# SpringReverbRev2_combined.net
KiCad netlist of a schematic drawn in EAGLE
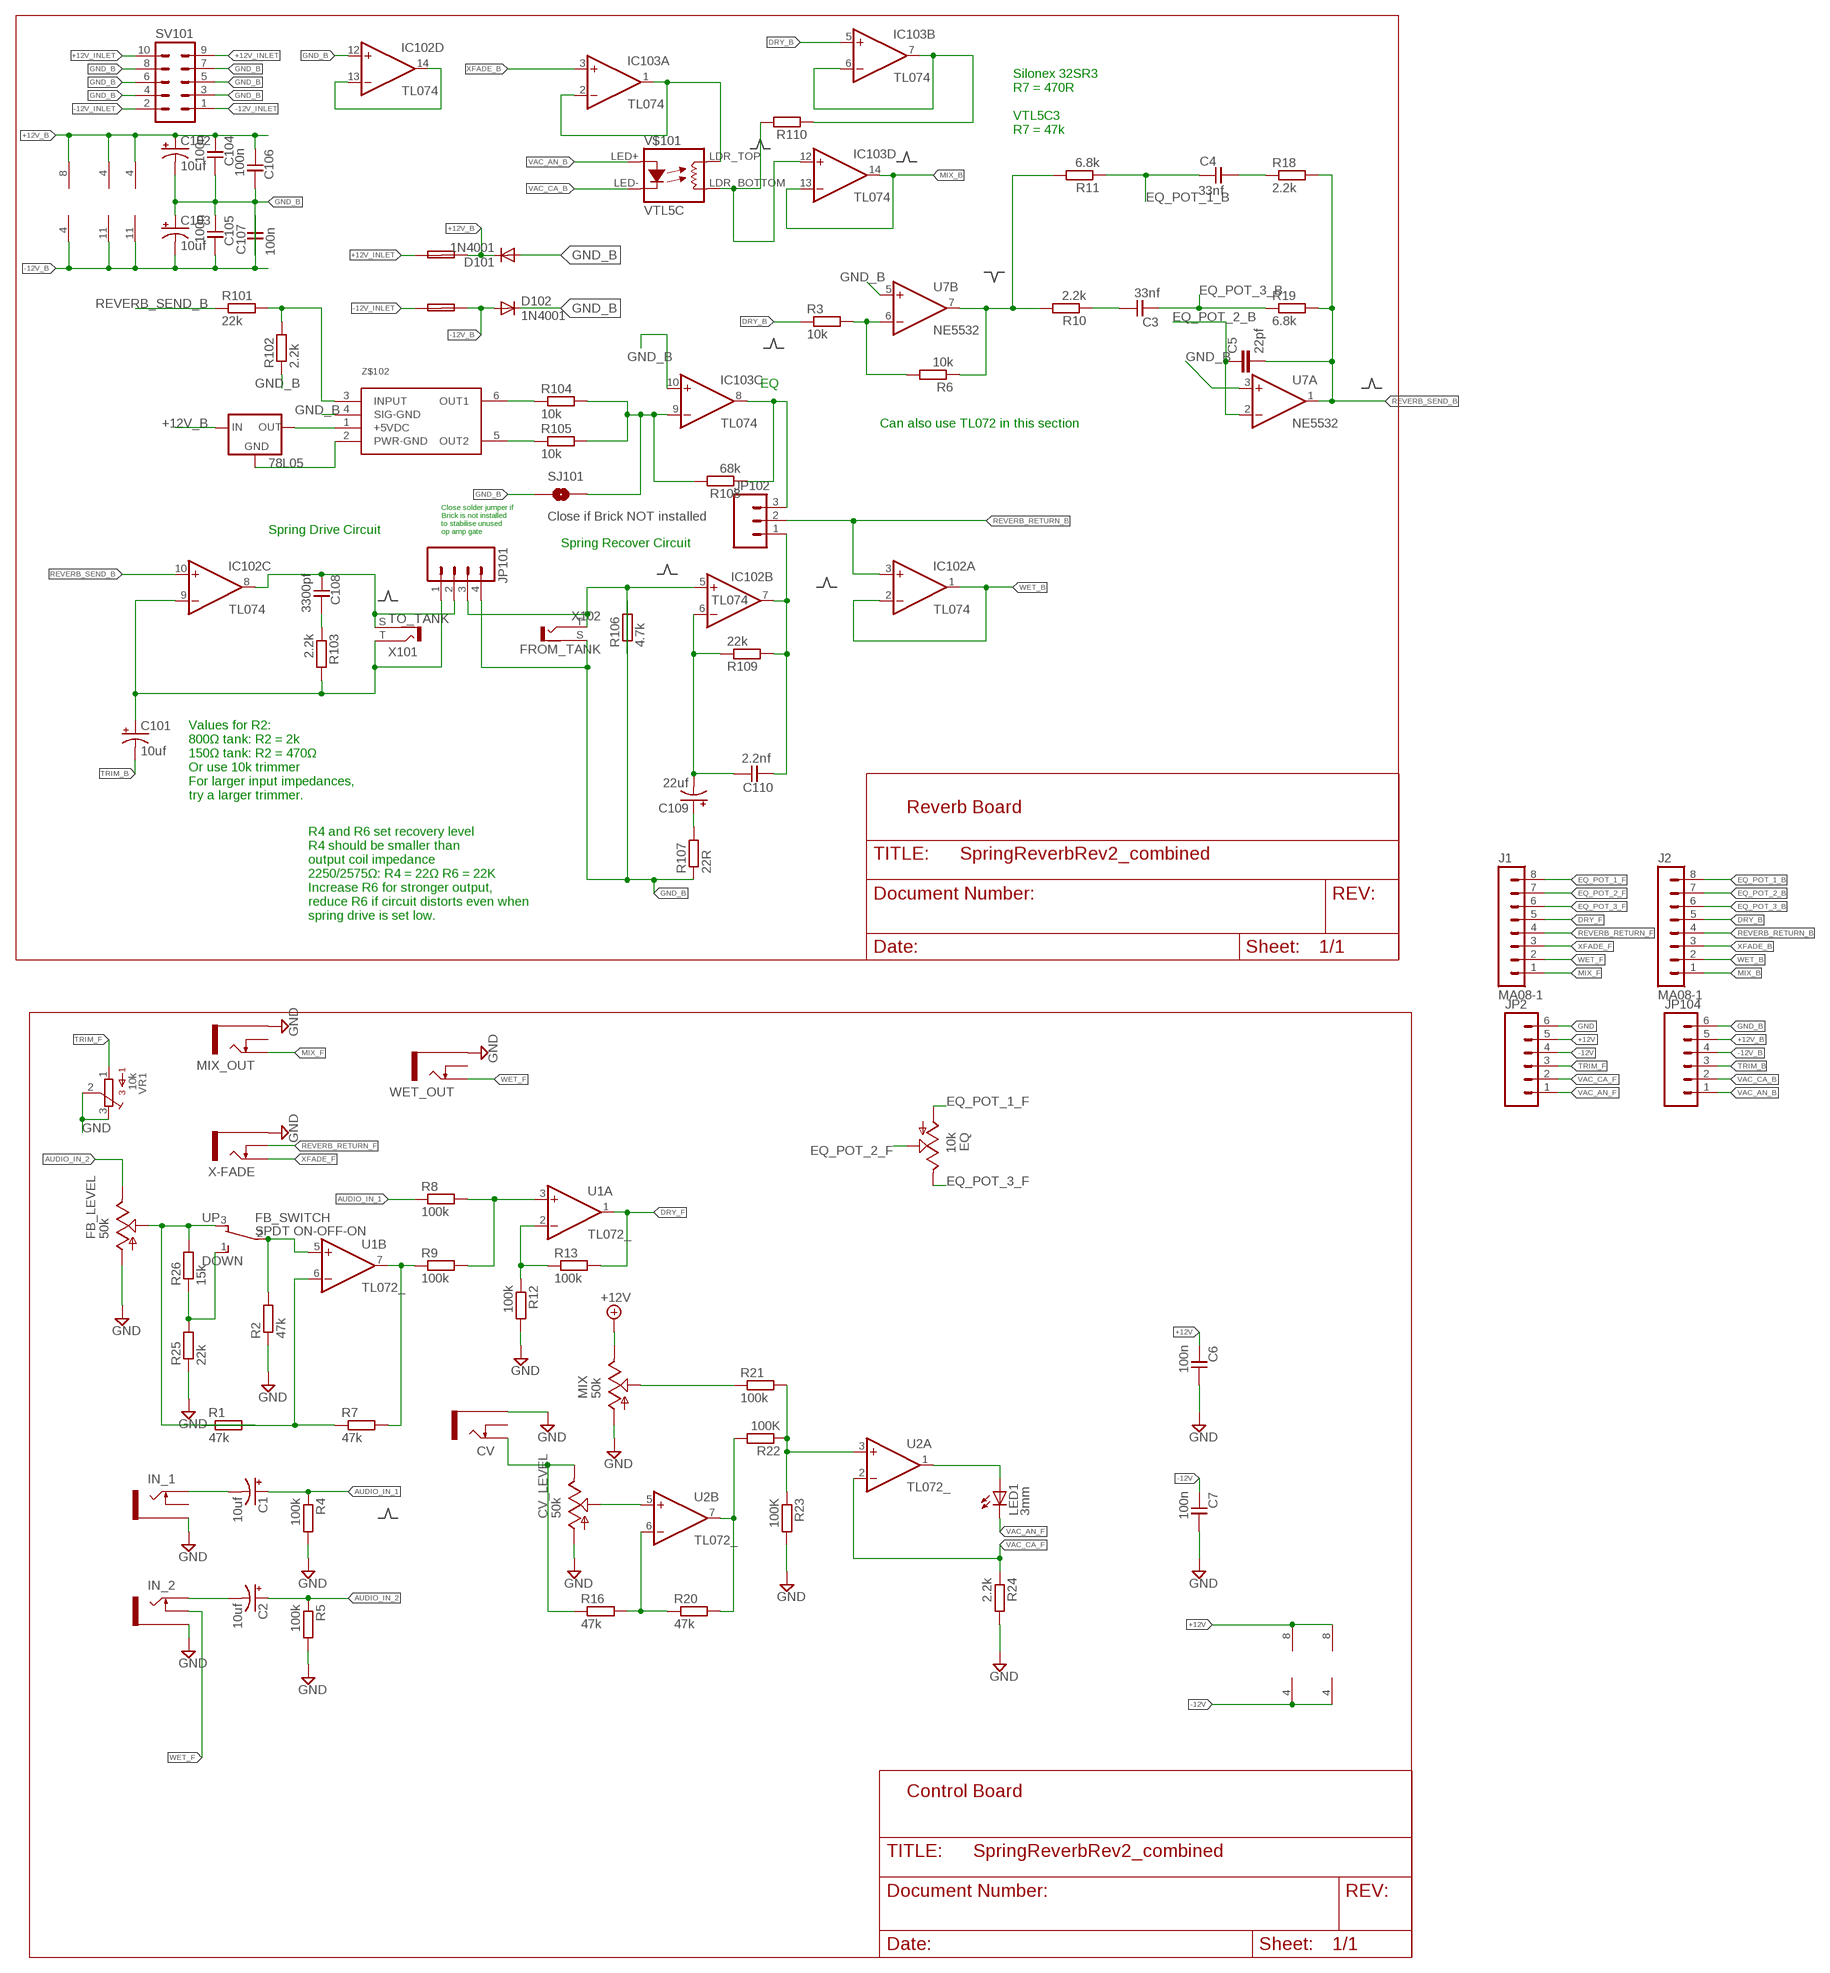
[diagram p0: schematic, sheet 1]

(export (version "E")
  (design (tool "Eeschema 10.0.6"))
  (components
    (comp (ref "78L05")
      (value "78LXX")
      (footprint "eagle-import:78LXX")
      (libsource (lib "eagle-import") (part "78LXX"))
    )
    (comp (ref "C1")
      (value "10uf")
      (footprint "eagle-import:050_020")
      (libsource (lib "eagle-import") (part "050"))
    )
    (comp (ref "C2")
      (value "10uf")
      (footprint "eagle-import:050_020")
      (libsource (lib "eagle-import") (part "050"))
    )
    (comp (ref "C3")
      (value "33nf")
      (footprint "eagle-import:C050-024X044")
      (libsource (lib "eagle-import") (part "C-EU050-024X044"))
    )
    (comp (ref "C4")
      (value "33nf")
      (footprint "eagle-import:C050-024X044")
      (libsource (lib "eagle-import") (part "C-EU050-024X044"))
    )
    (comp (ref "C5")
      (value "22pf")
      (footprint "eagle-import:050X030_025")
      (libsource (lib "eagle-import") (part "050X030_0251"))
    )
    (comp (ref "C6")
      (value "100n")
      (footprint "eagle-import:C050-024X044")
      (libsource (lib "eagle-import") (part "C-EU050-024X044"))
    )
    (comp (ref "C7")
      (value "100n")
      (footprint "eagle-import:C050-024X044")
      (libsource (lib "eagle-import") (part "C-EU050-024X044"))
    )
    (comp (ref "C101")
      (value "10uf")
      (footprint "eagle-import:CPOL-RADIAL-10UF-25V")
      (libsource (lib "eagle-import") (part "CAP_POLPTH2"))
    )
    (comp (ref "C102")
      (value "10uf")
      (footprint "eagle-import:CPOL-RADIAL-10UF-25V")
      (libsource (lib "eagle-import") (part "CAP_POLPTH2"))
    )
    (comp (ref "C103")
      (value "10uf")
      (footprint "eagle-import:CPOL-RADIAL-10UF-25V")
      (libsource (lib "eagle-import") (part "CAP_POLPTH2"))
    )
    (comp (ref "C104")
      (value "100n")
      (footprint "eagle-import:C050-024X044")
      (libsource (lib "eagle-import") (part "C-EU050-024X044"))
    )
    (comp (ref "C105")
      (value "100n")
      (footprint "eagle-import:C050-024X044")
      (libsource (lib "eagle-import") (part "C-EU050-024X044"))
    )
    (comp (ref "C106")
      (value "100n")
      (footprint "eagle-import:C050-024X044")
      (libsource (lib "eagle-import") (part "C-EU050-024X044"))
    )
    (comp (ref "C107")
      (value "100n")
      (footprint "eagle-import:C050-024X044")
      (libsource (lib "eagle-import") (part "C-EU050-024X044"))
    )
    (comp (ref "C108")
      (value "3300pf")
      (footprint "eagle-import:C050-024X044")
      (libsource (lib "eagle-import") (part "C-EU050-024X044"))
    )
    (comp (ref "C109")
      (value "22uf")
      (footprint "eagle-import:CPOL-RADIAL-10UF-25V")
      (libsource (lib "eagle-import") (part "CAP_POLPTH2"))
    )
    (comp (ref "C110")
      (value "2.2nf")
      (footprint "eagle-import:C050-024X044")
      (libsource (lib "eagle-import") (part "C-EU050-024X044"))
    )
    (comp (ref "CV")
      (value "THONKICONNNEW")
      (footprint "eagle-import:WQP-PJ301M-12_JACK")
      (libsource (lib "eagle-import") (part "THONKICONNNEW"))
    )
    (comp (ref "CV_LEVEL")
      (value "50k")
      (footprint "eagle-import:EVUF")
      (libsource (lib "eagle-import") (part "ALPHA-9MMAF2"))
    )
    (comp (ref "D101")
      (value "1N4001")
      (footprint "eagle-import:DO41-10")
      (libsource (lib "eagle-import") (part "1N4004"))
    )
    (comp (ref "D102")
      (value "1N4001")
      (footprint "eagle-import:DO41-10")
      (libsource (lib "eagle-import") (part "1N4004"))
    )
    (comp (ref "EQ")
      (value "10k")
      (footprint "eagle-import:EVUF")
      (libsource (lib "eagle-import") (part "ALPHA-9MMAF2"))
    )
    (comp (ref "F101")
      (value "FUSE")
      (footprint "eagle-import:C050H075X075")
      (libsource (lib "eagle-import") (part "PTC_FUSEPOLY_FUSE"))
    )
    (comp (ref "F102")
      (value "FUSE")
      (footprint "eagle-import:C050H075X075")
      (libsource (lib "eagle-import") (part "PTC_FUSEPOLY_FUSE"))
    )
    (comp (ref "FB_LEVEL")
      (value "50k")
      (footprint "eagle-import:EVUF")
      (libsource (lib "eagle-import") (part "ALPHA-9MMAF2"))
    )
    (comp (ref "FB_SWITCH")
      (value "SPDT ON-OFF-ON")
      (footprint "eagle-import:SPDT-VERTICAL-TOP-SUBMINI-MULTICOMP")
      (libsource (lib "eagle-import") (part "SPDT-VERTICAL-UPTOP-SUBMINI"))
    )
    (comp (ref "IC102")
      (value "TL074")
      (footprint "eagle-import:DIL14")
      (libsource (lib "eagle-import") (part "TL074P"))
    )
    (comp (ref "IC103")
      (value "TL074")
      (footprint "eagle-import:DIL14")
      (libsource (lib "eagle-import") (part "TL074P"))
    )
    (comp (ref "IN_1")
      (value "THONKICONNNEW")
      (footprint "eagle-import:WQP-PJ301M-12_JACK")
      (libsource (lib "eagle-import") (part "THONKICONNNEW"))
    )
    (comp (ref "IN_2")
      (value "THONKICONNNEW")
      (footprint "eagle-import:WQP-PJ301M-12_JACK")
      (libsource (lib "eagle-import") (part "THONKICONNNEW"))
    )
    (comp (ref "J1")
      (value "MA08-1")
      (footprint "eagle-import:MA08-1")
      (libsource (lib "eagle-import") (part "MA08-1"))
    )
    (comp (ref "J2")
      (value "MA08-1")
      (footprint "eagle-import:MA08-1")
      (libsource (lib "eagle-import") (part "MA08-1"))
    )
    (comp (ref "JP2")
      (value "M06SIP")
      (footprint "eagle-import:1X06")
      (libsource (lib "eagle-import") (part "M06SIP"))
    )
    (comp (ref "JP101")
      (value "M04POLAR")
      (footprint "eagle-import:MOLEX-1X4")
      (libsource (lib "eagle-import") (part "M04POLAR"))
    )
    (comp (ref "JP102")
      (value "M03LOCK_NO_SILK")
      (footprint "eagle-import:1X03_LOCK_NO_SILK")
      (libsource (lib "eagle-import") (part "M03LOCK_NO_SILK"))
    )
    (comp (ref "JP104")
      (value "M06SIP")
      (footprint "eagle-import:1X06")
      (libsource (lib "eagle-import") (part "M06SIP"))
    )
    (comp (ref "LED1")
      (value "3mm")
      (footprint "eagle-import:LED3MM")
      (libsource (lib "eagle-import") (part "LED3MM"))
    )
    (comp (ref "MIX")
      (value "50k")
      (footprint "eagle-import:EVUF")
      (libsource (lib "eagle-import") (part "ALPHA-9MMAF2"))
    )
    (comp (ref "MIX_OUT")
      (value "THONKICONNNEW")
      (footprint "eagle-import:WQP-PJ301M-12_JACK")
      (libsource (lib "eagle-import") (part "THONKICONNNEW"))
    )
    (comp (ref "R1")
      (value "47k")
      (footprint "eagle-import:7MM_RESISTOR")
      (libsource (lib "eagle-import") (part "RESISTOR7MM"))
    )
    (comp (ref "R2")
      (value "47k")
      (footprint "eagle-import:7MM_RESISTOR")
      (libsource (lib "eagle-import") (part "RESISTOR7MM"))
    )
    (comp (ref "R3")
      (value "10k")
      (footprint "eagle-import:7MM_RESISTOR")
      (libsource (lib "eagle-import") (part "RESISTOR7MM"))
    )
    (comp (ref "R4")
      (value "100k")
      (footprint "eagle-import:7MM_RESISTOR")
      (libsource (lib "eagle-import") (part "RESISTOR7MM"))
    )
    (comp (ref "R5")
      (value "100k")
      (footprint "eagle-import:7MM_RESISTOR")
      (libsource (lib "eagle-import") (part "RESISTOR7MM"))
    )
    (comp (ref "R6")
      (value "10k")
      (footprint "eagle-import:7MM_RESISTOR")
      (libsource (lib "eagle-import") (part "RESISTOR7MM"))
    )
    (comp (ref "R7")
      (value "47k")
      (footprint "eagle-import:7MM_RESISTOR")
      (libsource (lib "eagle-import") (part "RESISTOR7MM"))
    )
    (comp (ref "R8")
      (value "100k")
      (footprint "eagle-import:7MM_RESISTOR")
      (libsource (lib "eagle-import") (part "RESISTOR7MM"))
    )
    (comp (ref "R9")
      (value "100k")
      (footprint "eagle-import:7MM_RESISTOR")
      (libsource (lib "eagle-import") (part "RESISTOR7MM"))
    )
    (comp (ref "R10")
      (value "2.2k")
      (footprint "eagle-import:7MM_RESISTOR")
      (libsource (lib "eagle-import") (part "RESISTOR7MM"))
    )
    (comp (ref "R11")
      (value "6.8k")
      (footprint "eagle-import:7MM_RESISTOR")
      (libsource (lib "eagle-import") (part "RESISTOR7MM"))
    )
    (comp (ref "R12")
      (value "100k")
      (footprint "eagle-import:7MM_RESISTOR")
      (libsource (lib "eagle-import") (part "RESISTOR7MM"))
    )
    (comp (ref "R13")
      (value "100k")
      (footprint "eagle-import:7MM_RESISTOR")
      (libsource (lib "eagle-import") (part "RESISTOR7MM"))
    )
    (comp (ref "R16")
      (value "47k")
      (footprint "eagle-import:7MM_RESISTOR")
      (libsource (lib "eagle-import") (part "RESISTOR7MM"))
    )
    (comp (ref "R18")
      (value "2.2k")
      (footprint "eagle-import:7MM_RESISTOR")
      (libsource (lib "eagle-import") (part "RESISTOR7MM"))
    )
    (comp (ref "R19")
      (value "6.8k")
      (footprint "eagle-import:7MM_RESISTOR")
      (libsource (lib "eagle-import") (part "RESISTOR7MM"))
    )
    (comp (ref "R20")
      (value "47k")
      (footprint "eagle-import:7MM_RESISTOR")
      (libsource (lib "eagle-import") (part "RESISTOR7MM"))
    )
    (comp (ref "R21")
      (value "100k")
      (footprint "eagle-import:7MM_RESISTOR")
      (libsource (lib "eagle-import") (part "RESISTOR7MM"))
    )
    (comp (ref "R22")
      (value "100K")
      (footprint "eagle-import:7MM_RESISTOR")
      (libsource (lib "eagle-import") (part "RESISTOR7MM"))
    )
    (comp (ref "R23")
      (value "100K")
      (footprint "eagle-import:7MM_RESISTOR")
      (libsource (lib "eagle-import") (part "RESISTOR7MM"))
    )
    (comp (ref "R24")
      (value "2.2k")
      (footprint "eagle-import:7MM_RESISTOR")
      (libsource (lib "eagle-import") (part "RESISTOR7MM"))
    )
    (comp (ref "R25")
      (value "22k")
      (footprint "eagle-import:7MM_RESISTOR")
      (libsource (lib "eagle-import") (part "RESISTOR7MM"))
    )
    (comp (ref "R26")
      (value "15k")
      (footprint "eagle-import:7MM_RESISTOR")
      (libsource (lib "eagle-import") (part "RESISTOR7MM"))
    )
    (comp (ref "R101")
      (value "22k")
      (footprint "eagle-import:7MM_RESISTOR")
      (libsource (lib "eagle-import") (part "RESISTOR7MM"))
    )
    (comp (ref "R102")
      (value "2.2k")
      (footprint "eagle-import:7MM_RESISTOR")
      (libsource (lib "eagle-import") (part "RESISTOR7MM"))
    )
    (comp (ref "R103")
      (value "2.2k")
      (footprint "eagle-import:7MM_RESISTOR")
      (libsource (lib "eagle-import") (part "RESISTOR7MM"))
    )
    (comp (ref "R104")
      (value "10k")
      (footprint "eagle-import:7MM_RESISTOR")
      (libsource (lib "eagle-import") (part "RESISTOR7MM"))
    )
    (comp (ref "R105")
      (value "10k")
      (footprint "eagle-import:7MM_RESISTOR")
      (libsource (lib "eagle-import") (part "RESISTOR7MM"))
    )
    (comp (ref "R106")
      (value "4.7k")
      (footprint "eagle-import:7MM_RESISTOR")
      (libsource (lib "eagle-import") (part "RESISTOR7MM"))
    )
    (comp (ref "R107")
      (value "22R")
      (footprint "eagle-import:7MM_RESISTOR")
      (libsource (lib "eagle-import") (part "RESISTOR7MM"))
    )
    (comp (ref "R108")
      (value "68k")
      (footprint "eagle-import:7MM_RESISTOR")
      (libsource (lib "eagle-import") (part "RESISTOR7MM"))
    )
    (comp (ref "R109")
      (value "22k")
      (footprint "eagle-import:7MM_RESISTOR")
      (libsource (lib "eagle-import") (part "RESISTOR7MM"))
    )
    (comp (ref "R110")
      (value "RESISTOR7MM")
      (footprint "eagle-import:7MM_RESISTOR")
      (libsource (lib "eagle-import") (part "RESISTOR7MM"))
    )
    (comp (ref "SJ101")
      (value "Close if Brick NOT installed")
      (footprint "eagle-import:SJ_2S-NOTRACE")
      (libsource (lib "eagle-import") (part "SOLDERJUMPERNC2"))
    )
    (comp (ref "SV101")
      (value "10_PIN_HEADER")
      (footprint "eagle-import:MA05-2")
      (libsource (lib "eagle-import") (part "10_PIN_HEADER"))
    )
    (comp (ref "U1")
      (value "TL072_")
      (footprint "eagle-import:DIL08")
      (libsource (lib "eagle-import") (part "TL072_"))
    )
    (comp (ref "U2")
      (value "TL072_")
      (footprint "eagle-import:DIL08")
      (libsource (lib "eagle-import") (part "TL072_"))
    )
    (comp (ref "U7")
      (value "NE5532")
      (footprint "eagle-import:DIL08")
      (libsource (lib "eagle-import") (part "TL072_"))
    )
    (comp (ref "V$101")
      (value "VTL5C")
      (footprint "eagle-import:VACTROL_COMPACT")
      (libsource (lib "eagle-import") (part "VACTROL_COMPACT"))
    )
    (comp (ref "VR1")
      (value "10k")
      (footprint "eagle-import:BOURNS_3362P_TRIMMER")
      (libsource (lib "eagle-import") (part "BOURNS_3362P_TRIMMERP"))
    )
    (comp (ref "WET_OUT")
      (value "THONKICONNNEW")
      (footprint "eagle-import:WQP-PJ301M-12_JACK")
      (libsource (lib "eagle-import") (part "THONKICONNNEW"))
    )
    (comp (ref "X-FADE")
      (value "THONKICONNNEW")
      (footprint "eagle-import:WQP-PJ301M-12_JACK")
      (libsource (lib "eagle-import") (part "THONKICONNNEW"))
    )
    (comp (ref "X101")
      (value "TO_TANK")
      (footprint "eagle-import:BTOR1")
      (fields (field (name "MPN") "BTOR 1"))
      (libsource (lib "eagle-import") (part "BTOR1"))
    )
    (comp (ref "X102")
      (value "FROM_TANK")
      (footprint "eagle-import:BTOR1")
      (fields (field (name "MPN") "BTOR 1"))
      (libsource (lib "eagle-import") (part "BTOR1"))
    )
    (comp (ref "Z$102")
      (value "BTDR-2H")
      (footprint "eagle-import:BTDR-2H")
      (libsource (lib "eagle-import") (part "BTDR-2H"))
    )
  )
  (nets
    (net (code "1") (name "+12V") (class "Default")
      (node (ref "C6") (pin "2") (pinfunction "2_2") (pintype "passive"))
      (node (ref "JP2") (pin "5") (pinfunction "5_5") (pintype "passive"))
      (node (ref "MIX") (pin "3") (pinfunction "E_3") (pintype "passive"))
      (node (ref "U1") (pin "8") (pinfunction "V+_8") (pintype "power_in"))
      (node (ref "U2") (pin "8") (pinfunction "V+_8") (pintype "power_in"))
    )
    (net (code "2") (name "+12V_B") (class "Default")
      (node (ref "78L05") (pin "IN") (pinfunction "IN_IN") (pintype "input"))
      (node (ref "C102") (pin "1") (pinfunction "+_1") (pintype "passive"))
      (node (ref "C104") (pin "2") (pinfunction "2_2") (pintype "passive"))
      (node (ref "C106") (pin "2") (pinfunction "2_2") (pintype "passive"))
      (node (ref "D101") (pin "C") (pinfunction "C_C") (pintype "passive"))
      (node (ref "F101") (pin "1") (pinfunction "P$1_1") (pintype "bidirectional"))
      (node (ref "IC102") (pin "4") (pinfunction "V+_4") (pintype "power_in"))
      (node (ref "IC103") (pin "4") (pinfunction "V+_4") (pintype "power_in"))
      (node (ref "JP104") (pin "5") (pinfunction "5_5") (pintype "passive"))
      (node (ref "U7") (pin "8") (pinfunction "V+_8") (pintype "power_in"))
    )
    (net (code "3") (name "+12V_INLET") (class "Default")
      (node (ref "F101") (pin "2") (pinfunction "P$2_2") (pintype "bidirectional"))
      (node (ref "SV101") (pin "10") (pinfunction "10_10") (pintype "passive"))
      (node (ref "SV101") (pin "9") (pinfunction "9_9") (pintype "passive"))
    )
    (net (code "4") (name "-12V") (class "Default")
      (node (ref "C7") (pin "2") (pinfunction "2_2") (pintype "passive"))
      (node (ref "JP2") (pin "4") (pinfunction "4_4") (pintype "passive"))
      (node (ref "U1") (pin "4") (pinfunction "V-_4") (pintype "power_in"))
      (node (ref "U2") (pin "4") (pinfunction "V-_4") (pintype "power_in"))
    )
    (net (code "5") (name "-12V_B") (class "Default")
      (node (ref "C103") (pin "2") (pinfunction "-_2") (pintype "passive"))
      (node (ref "C105") (pin "1") (pinfunction "1_1") (pintype "passive"))
      (node (ref "C107") (pin "1") (pinfunction "1_1") (pintype "passive"))
      (node (ref "D102") (pin "A") (pinfunction "A_A") (pintype "passive"))
      (node (ref "F102") (pin "1") (pinfunction "P$1_1") (pintype "bidirectional"))
      (node (ref "IC102") (pin "11") (pinfunction "V-_11") (pintype "power_in"))
      (node (ref "IC103") (pin "11") (pinfunction "V-_11") (pintype "power_in"))
      (node (ref "JP104") (pin "4") (pinfunction "4_4") (pintype "passive"))
      (node (ref "U7") (pin "4") (pinfunction "V-_4") (pintype "power_in"))
    )
    (net (code "6") (name "-12V_INLET") (class "Default")
      (node (ref "F102") (pin "2") (pinfunction "P$2_2") (pintype "bidirectional"))
      (node (ref "SV101") (pin "1") (pinfunction "1_1") (pintype "passive"))
      (node (ref "SV101") (pin "2") (pinfunction "2_2") (pintype "passive"))
    )
    (net (code "7") (name "AUDIO_IN_1") (class "Default")
      (node (ref "C1") (pin "+") (pinfunction "+_+") (pintype "passive"))
      (node (ref "R4") (pin "1") (pinfunction "1_1") (pintype "passive"))
      (node (ref "R8") (pin "1") (pinfunction "1_1") (pintype "passive"))
    )
    (net (code "8") (name "AUDIO_IN_2") (class "Default")
      (node (ref "C2") (pin "+") (pinfunction "+_+") (pintype "passive"))
      (node (ref "FB_LEVEL") (pin "3") (pinfunction "E_3") (pintype "passive"))
      (node (ref "R5") (pin "1") (pinfunction "1_1") (pintype "passive"))
    )
    (net (code "9") (name "DRY_B") (class "Default")
      (node (ref "IC103") (pin "5") (pinfunction "+IN_5") (pintype "input"))
      (node (ref "J2") (pin "5") (pinfunction "5_5") (pintype "passive"))
      (node (ref "R3") (pin "1") (pinfunction "1_1") (pintype "passive"))
    )
    (net (code "10") (name "DRY_F") (class "Default")
      (node (ref "J1") (pin "5") (pinfunction "5_5") (pintype "passive"))
      (node (ref "R13") (pin "2") (pinfunction "2_2") (pintype "passive"))
      (node (ref "U1") (pin "1") (pinfunction "OUT_1") (pintype "output"))
    )
    (net (code "11") (name "EQ_POT_1_B") (class "Default")
      (node (ref "C4") (pin "2") (pinfunction "2_2") (pintype "passive"))
      (node (ref "J2") (pin "8") (pinfunction "8_8") (pintype "passive"))
      (node (ref "R11") (pin "1") (pinfunction "1_1") (pintype "passive"))
    )
    (net (code "12") (name "EQ_POT_1_F") (class "Default")
      (node (ref "EQ") (pin "1") (pinfunction "A_1") (pintype "passive"))
      (node (ref "J1") (pin "8") (pinfunction "8_8") (pintype "passive"))
    )
    (net (code "13") (name "EQ_POT_2_B") (class "Default")
      (node (ref "C5") (pin "1") (pinfunction "1_1") (pintype "passive"))
      (node (ref "J2") (pin "7") (pinfunction "7_7") (pintype "passive"))
      (node (ref "U7") (pin "2") (pinfunction "-IN_2") (pintype "input"))
    )
    (net (code "14") (name "EQ_POT_2_F") (class "Default")
      (node (ref "EQ") (pin "2") (pinfunction "S_2") (pintype "passive"))
      (node (ref "J1") (pin "7") (pinfunction "7_7") (pintype "passive"))
    )
    (net (code "15") (name "EQ_POT_3_B") (class "Default")
      (node (ref "C3") (pin "2") (pinfunction "2_2") (pintype "passive"))
      (node (ref "J2") (pin "6") (pinfunction "6_6") (pintype "passive"))
      (node (ref "R19") (pin "1") (pinfunction "1_1") (pintype "passive"))
    )
    (net (code "16") (name "EQ_POT_3_F") (class "Default")
      (node (ref "EQ") (pin "3") (pinfunction "E_3") (pintype "passive"))
      (node (ref "J1") (pin "6") (pinfunction "6_6") (pintype "passive"))
    )
    (net (code "17") (name "GND") (class "Default")
      (node (ref "C6") (pin "1") (pinfunction "1_1") (pintype "passive"))
      (node (ref "C7") (pin "1") (pinfunction "1_1") (pintype "passive"))
      (node (ref "CV") (pin "P$3_SLEEVE") (pinfunction "SLEEVE_P$3_SLEEVE") (pintype "passive"))
      (node (ref "CV_LEVEL") (pin "1") (pinfunction "A_1") (pintype "passive"))
      (node (ref "FB_LEVEL") (pin "1") (pinfunction "A_1") (pintype "passive"))
      (node (ref "IN_1") (pin "P$3_SLEEVE") (pinfunction "SLEEVE_P$3_SLEEVE") (pintype "passive"))
      (node (ref "IN_2") (pin "P$3_SLEEVE") (pinfunction "SLEEVE_P$3_SLEEVE") (pintype "passive"))
      (node (ref "JP2") (pin "6") (pinfunction "6_6") (pintype "passive"))
      (node (ref "MIX") (pin "1") (pinfunction "A_1") (pintype "passive"))
      (node (ref "MIX_OUT") (pin "P$3_SLEEVE") (pinfunction "SLEEVE_P$3_SLEEVE") (pintype "passive"))
      (node (ref "R12") (pin "2") (pinfunction "2_2") (pintype "passive"))
      (node (ref "R2") (pin "1") (pinfunction "1_1") (pintype "passive"))
      (node (ref "R23") (pin "2") (pinfunction "2_2") (pintype "passive"))
      (node (ref "R24") (pin "2") (pinfunction "2_2") (pintype "passive"))
      (node (ref "R25") (pin "1") (pinfunction "1_1") (pintype "passive"))
      (node (ref "R4") (pin "2") (pinfunction "2_2") (pintype "passive"))
      (node (ref "R5") (pin "2") (pinfunction "2_2") (pintype "passive"))
      (node (ref "VR1") (pin "2") (pinfunction "2_2") (pintype "passive"))
      (node (ref "VR1") (pin "3") (pinfunction "3_3") (pintype "passive"))
      (node (ref "WET_OUT") (pin "P$3_SLEEVE") (pinfunction "SLEEVE_P$3_SLEEVE") (pintype "passive"))
      (node (ref "X-FADE") (pin "P$3_SLEEVE") (pinfunction "SLEEVE_P$3_SLEEVE") (pintype "passive"))
    )
    (net (code "18") (name "GND_B") (class "Default")
      (node (ref "C102") (pin "2") (pinfunction "-_2") (pintype "passive"))
      (node (ref "C103") (pin "1") (pinfunction "+_1") (pintype "passive"))
      (node (ref "C104") (pin "1") (pinfunction "1_1") (pintype "passive"))
      (node (ref "C105") (pin "2") (pinfunction "2_2") (pintype "passive"))
      (node (ref "C106") (pin "1") (pinfunction "1_1") (pintype "passive"))
      (node (ref "C107") (pin "2") (pinfunction "2_2") (pintype "passive"))
      (node (ref "D101") (pin "A") (pinfunction "A_A") (pintype "passive"))
      (node (ref "D102") (pin "C") (pinfunction "C_C") (pintype "passive"))
      (node (ref "IC102") (pin "12") (pinfunction "+IN_12") (pintype "input"))
      (node (ref "IC103") (pin "10") (pinfunction "+IN_10") (pintype "input"))
      (node (ref "JP101") (pin "4") (pinfunction "4_4") (pintype "passive"))
      (node (ref "JP104") (pin "6") (pinfunction "6_6") (pintype "passive"))
      (node (ref "R102") (pin "1") (pinfunction "1_1") (pintype "passive"))
      (node (ref "R106") (pin "2") (pinfunction "2_2") (pintype "passive"))
      (node (ref "R107") (pin "1") (pinfunction "1_1") (pintype "passive"))
      (node (ref "SJ101") (pin "1") (pinfunction "1_1") (pintype "passive"))
      (node (ref "SV101") (pin "3") (pinfunction "3_3") (pintype "passive"))
      (node (ref "SV101") (pin "4") (pinfunction "4_4") (pintype "passive"))
      (node (ref "SV101") (pin "5") (pinfunction "5_5") (pintype "passive"))
      (node (ref "SV101") (pin "6") (pinfunction "6_6") (pintype "passive"))
      (node (ref "SV101") (pin "7") (pinfunction "7_7") (pintype "passive"))
      (node (ref "SV101") (pin "8") (pinfunction "8_8") (pintype "passive"))
      (node (ref "U7") (pin "3") (pinfunction "+IN_3") (pintype "input"))
      (node (ref "U7") (pin "5") (pinfunction "+IN_5") (pintype "input"))
      (node (ref "X102") (pin "S") (pinfunction "2_S") (pintype "passive"))
      (node (ref "Z$102") (pin "4") (pinfunction "SIG-GND_4") (pintype "bidirectional"))
    )
    (net (code "19") (name "MIX_B") (class "Default")
      (node (ref "IC103") (pin "13") (pinfunction "-IN_13") (pintype "input"))
      (node (ref "IC103") (pin "14") (pinfunction "OUT_14") (pintype "output"))
      (node (ref "J2") (pin "1") (pinfunction "1_1") (pintype "passive"))
    )
    (net (code "20") (name "MIX_F") (class "Default")
      (node (ref "J1") (pin "1") (pinfunction "1_1") (pintype "passive"))
      (node (ref "MIX_OUT") (pin "P$1_TIP") (pinfunction "TIP_P$1_TIP") (pintype "passive"))
    )
    (net (code "21") (name "Net-(C3-Pad1)") (class "Default")
      (node (ref "C3") (pin "1") (pinfunction "1_1") (pintype "passive"))
      (node (ref "R10") (pin "1") (pinfunction "1_1") (pintype "passive"))
    )
    (net (code "22") (name "Net-(C4-Pad1)") (class "Default")
      (node (ref "C4") (pin "1") (pinfunction "1_1") (pintype "passive"))
      (node (ref "R18") (pin "1") (pinfunction "1_1") (pintype "passive"))
    )
    (net (code "23") (name "Net-(C101-+)") (class "Default")
      (node (ref "C101") (pin "1") (pinfunction "+_1") (pintype "passive"))
      (node (ref "IC102") (pin "9") (pinfunction "-IN_9") (pintype "input"))
      (node (ref "JP101") (pin "1") (pinfunction "1_1") (pintype "passive"))
      (node (ref "R103") (pin "2") (pinfunction "2_2") (pintype "passive"))
      (node (ref "X101") (pin "T") (pinfunction "1_T") (pintype "passive"))
    )
    (net (code "24") (name "Net-(C108-Pad1)") (class "Default")
      (node (ref "C108") (pin "1") (pinfunction "1_1") (pintype "passive"))
      (node (ref "R103") (pin "1") (pinfunction "1_1") (pintype "passive"))
    )
    (net (code "25") (name "Net-(C109-+)") (class "Default")
      (node (ref "C109") (pin "1") (pinfunction "+_1") (pintype "passive"))
      (node (ref "R107") (pin "2") (pinfunction "2_2") (pintype "passive"))
    )
    (net (code "26") (name "Net-(C109--)") (class "Default")
      (node (ref "C109") (pin "2") (pinfunction "-_2") (pintype "passive"))
      (node (ref "C110") (pin "1") (pinfunction "1_1") (pintype "passive"))
      (node (ref "IC102") (pin "6") (pinfunction "-IN_6") (pintype "input"))
      (node (ref "R109") (pin "1") (pinfunction "1_1") (pintype "passive"))
    )
    (net (code "27") (name "Net-(CV-TIP)") (class "Default")
      (node (ref "CV") (pin "P$1_TIP") (pinfunction "TIP_P$1_TIP") (pintype "passive"))
      (node (ref "CV_LEVEL") (pin "3") (pinfunction "E_3") (pintype "passive"))
      (node (ref "R16") (pin "1") (pinfunction "1_1") (pintype "passive"))
    )
    (net (code "28") (name "Net-(CV_LEVEL-S)") (class "Default")
      (node (ref "CV_LEVEL") (pin "2") (pinfunction "S_2") (pintype "passive"))
      (node (ref "U2") (pin "5") (pinfunction "+IN_5") (pintype "input"))
    )
    (net (code "29") (name "Net-(FB_LEVEL-S)") (class "Default")
      (node (ref "FB_LEVEL") (pin "2") (pinfunction "S_2") (pintype "passive"))
      (node (ref "FB_SWITCH") (pin "3") (pinfunction "3_3") (pintype "passive"))
      (node (ref "R1") (pin "2") (pinfunction "2_2") (pintype "passive"))
      (node (ref "R26") (pin "2") (pinfunction "2_2") (pintype "passive"))
    )
    (net (code "30") (name "Net-(FB_SWITCH-Pad1)") (class "Default")
      (node (ref "FB_SWITCH") (pin "1") (pinfunction "1_1") (pintype "passive"))
      (node (ref "R25") (pin "2") (pinfunction "2_2") (pintype "passive"))
      (node (ref "R26") (pin "1") (pinfunction "1_1") (pintype "passive"))
    )
    (net (code "31") (name "Net-(IC102B-+IN)") (class "Default")
      (node (ref "IC102") (pin "5") (pinfunction "+IN_5") (pintype "input"))
      (node (ref "JP101") (pin "3") (pinfunction "3_3") (pintype "passive"))
      (node (ref "R106") (pin "1") (pinfunction "1_1") (pintype "passive"))
      (node (ref "X102") (pin "T") (pinfunction "1_T") (pintype "passive"))
    )
    (net (code "32") (name "Net-(IC102B-OUT)") (class "Default")
      (node (ref "C110") (pin "2") (pinfunction "2_2") (pintype "passive"))
      (node (ref "IC102") (pin "7") (pinfunction "OUT_7") (pintype "output"))
      (node (ref "JP102") (pin "1") (pinfunction "1_1") (pintype "passive"))
      (node (ref "R109") (pin "2") (pinfunction "2_2") (pintype "passive"))
    )
    (net (code "33") (name "Net-(IC102C-OUT)") (class "Default")
      (node (ref "C108") (pin "2") (pinfunction "2_2") (pintype "passive"))
      (node (ref "IC102") (pin "8") (pinfunction "OUT_8") (pintype "output"))
      (node (ref "JP101") (pin "2") (pinfunction "2_2") (pintype "passive"))
      (node (ref "X101") (pin "S") (pinfunction "2_S") (pintype "passive"))
    )
    (net (code "34") (name "Net-(IC102D--IN)") (class "Default")
      (node (ref "IC102") (pin "13") (pinfunction "-IN_13") (pintype "input"))
      (node (ref "IC102") (pin "14") (pinfunction "OUT_14") (pintype "output"))
    )
    (net (code "35") (name "Net-(IC103A--IN)") (class "Default")
      (node (ref "IC103") (pin "1") (pinfunction "OUT_1") (pintype "output"))
      (node (ref "IC103") (pin "2") (pinfunction "-IN_2") (pintype "input"))
      (node (ref "V$101") (pin "LDR_TOP") (pinfunction "RES1_LDR_TOP") (pintype "passive"))
    )
    (net (code "36") (name "Net-(IC103B--IN)") (class "Default")
      (node (ref "IC103") (pin "6") (pinfunction "-IN_6") (pintype "input"))
      (node (ref "IC103") (pin "7") (pinfunction "OUT_7") (pintype "output"))
      (node (ref "R110") (pin "1") (pinfunction "1_1") (pintype "passive"))
    )
    (net (code "37") (name "Net-(IC103C--IN)") (class "Default")
      (node (ref "IC103") (pin "9") (pinfunction "-IN_9") (pintype "input"))
      (node (ref "R104") (pin "2") (pinfunction "2_2") (pintype "passive"))
      (node (ref "R105") (pin "2") (pinfunction "2_2") (pintype "passive"))
      (node (ref "R108") (pin "2") (pinfunction "2_2") (pintype "passive"))
      (node (ref "SJ101") (pin "2") (pinfunction "2_2") (pintype "passive"))
    )
    (net (code "38") (name "Net-(IC103C-OUT)") (class "Default")
      (node (ref "IC103") (pin "8") (pinfunction "OUT_8") (pintype "output"))
      (node (ref "JP102") (pin "3") (pinfunction "3_3") (pintype "passive"))
      (node (ref "R108") (pin "1") (pinfunction "1_1") (pintype "passive"))
    )
    (net (code "39") (name "Net-(IC103D-+IN)") (class "Default")
      (node (ref "IC103") (pin "12") (pinfunction "+IN_12") (pintype "input"))
      (node (ref "R110") (pin "2") (pinfunction "2_2") (pintype "passive"))
      (node (ref "V$101") (pin "LDR_BOTTOM") (pinfunction "RES2_LDR_BOTTOM") (pintype "passive"))
    )
    (net (code "40") (name "Net-(IN_1-TIP)") (class "Default")
      (node (ref "C1") (pin "-") (pinfunction "-_-") (pintype "passive"))
      (node (ref "IN_1") (pin "P$1_TIP") (pinfunction "TIP_P$1_TIP") (pintype "passive"))
    )
    (net (code "41") (name "Net-(IN_2-TIP)") (class "Default")
      (node (ref "C2") (pin "-") (pinfunction "-_-") (pintype "passive"))
      (node (ref "IN_2") (pin "P$1_TIP") (pinfunction "TIP_P$1_TIP") (pintype "passive"))
    )
    (net (code "42") (name "Net-(MIX-S)") (class "Default")
      (node (ref "MIX") (pin "2") (pinfunction "S_2") (pintype "passive"))
      (node (ref "R21") (pin "1") (pinfunction "1_1") (pintype "passive"))
    )
    (net (code "43") (name "Net-(U1A-+IN)") (class "Default")
      (node (ref "R8") (pin "2") (pinfunction "2_2") (pintype "passive"))
      (node (ref "R9") (pin "2") (pinfunction "2_2") (pintype "passive"))
      (node (ref "U1") (pin "3") (pinfunction "+IN_3") (pintype "input"))
    )
    (net (code "44") (name "Net-(U1A--IN)") (class "Default")
      (node (ref "R12") (pin "1") (pinfunction "1_1") (pintype "passive"))
      (node (ref "R13") (pin "1") (pinfunction "1_1") (pintype "passive"))
      (node (ref "U1") (pin "2") (pinfunction "-IN_2") (pintype "input"))
    )
    (net (code "45") (name "Net-(U1B-+IN)") (class "Default")
      (node (ref "FB_SWITCH") (pin "2") (pinfunction "2_2") (pintype "passive"))
      (node (ref "R2") (pin "2") (pinfunction "2_2") (pintype "passive"))
      (node (ref "U1") (pin "5") (pinfunction "+IN_5") (pintype "input"))
    )
    (net (code "46") (name "Net-(U1B--IN)") (class "Default")
      (node (ref "R1") (pin "1") (pinfunction "1_1") (pintype "passive"))
      (node (ref "R7") (pin "1") (pinfunction "1_1") (pintype "passive"))
      (node (ref "U1") (pin "6") (pinfunction "-IN_6") (pintype "input"))
    )
    (net (code "47") (name "Net-(U1B-OUT)") (class "Default")
      (node (ref "R7") (pin "2") (pinfunction "2_2") (pintype "passive"))
      (node (ref "R9") (pin "1") (pinfunction "1_1") (pintype "passive"))
      (node (ref "U1") (pin "7") (pinfunction "OUT_7") (pintype "output"))
    )
    (net (code "48") (name "Net-(U2A-+IN)") (class "Default")
      (node (ref "R21") (pin "2") (pinfunction "2_2") (pintype "passive"))
      (node (ref "R22") (pin "1") (pinfunction "1_1") (pintype "passive"))
      (node (ref "R23") (pin "1") (pinfunction "1_1") (pintype "passive"))
      (node (ref "U2") (pin "3") (pinfunction "+IN_3") (pintype "input"))
    )
    (net (code "49") (name "Net-(U2A-OUT)") (class "Default")
      (node (ref "LED1") (pin "A") (pinfunction "A_A") (pintype "passive"))
      (node (ref "U2") (pin "1") (pinfunction "OUT_1") (pintype "output"))
    )
    (net (code "50") (name "Net-(U2B--IN)") (class "Default")
      (node (ref "R16") (pin "2") (pinfunction "2_2") (pintype "passive"))
      (node (ref "R20") (pin "1") (pinfunction "1_1") (pintype "passive"))
      (node (ref "U2") (pin "6") (pinfunction "-IN_6") (pintype "input"))
    )
    (net (code "51") (name "Net-(U2B-OUT)") (class "Default")
      (node (ref "R20") (pin "2") (pinfunction "2_2") (pintype "passive"))
      (node (ref "R22") (pin "2") (pinfunction "2_2") (pintype "passive"))
      (node (ref "U2") (pin "7") (pinfunction "OUT_7") (pintype "output"))
    )
    (net (code "52") (name "Net-(U7B--IN)") (class "Default")
      (node (ref "R3") (pin "2") (pinfunction "2_2") (pintype "passive"))
      (node (ref "R6") (pin "2") (pinfunction "2_2") (pintype "passive"))
      (node (ref "U7") (pin "6") (pinfunction "-IN_6") (pintype "input"))
    )
    (net (code "53") (name "Net-(U7B-OUT)") (class "Default")
      (node (ref "R10") (pin "2") (pinfunction "2_2") (pintype "passive"))
      (node (ref "R11") (pin "2") (pinfunction "2_2") (pintype "passive"))
      (node (ref "R6") (pin "1") (pinfunction "1_1") (pintype "passive"))
      (node (ref "U7") (pin "7") (pinfunction "OUT_7") (pintype "output"))
    )
    (net (code "54") (name "Net-(Z$102-+5VDC)") (class "Default")
      (node (ref "78L05") (pin "OUT") (pinfunction "OUT_OUT") (pintype "passive"))
      (node (ref "Z$102") (pin "1") (pinfunction "+5VDC_1") (pintype "bidirectional"))
    )
    (net (code "55") (name "Net-(Z$102-INPUT)") (class "Default")
      (node (ref "R101") (pin "2") (pinfunction "2_2") (pintype "passive"))
      (node (ref "R102") (pin "2") (pinfunction "2_2") (pintype "passive"))
      (node (ref "Z$102") (pin "3") (pinfunction "INPUT_3") (pintype "bidirectional"))
    )
    (net (code "56") (name "Net-(Z$102-OUT1)") (class "Default")
      (node (ref "R104") (pin "1") (pinfunction "1_1") (pintype "passive"))
      (node (ref "Z$102") (pin "6") (pinfunction "OUT1_6") (pintype "bidirectional"))
    )
    (net (code "57") (name "Net-(Z$102-OUT2)") (class "Default")
      (node (ref "R105") (pin "1") (pinfunction "1_1") (pintype "passive"))
      (node (ref "Z$102") (pin "5") (pinfunction "OUT2_5") (pintype "bidirectional"))
    )
    (net (code "58") (name "Net-(Z$102-PWR-GND)") (class "Default")
      (node (ref "78L05") (pin "GND") (pinfunction "GND_GND") (pintype "input"))
      (node (ref "Z$102") (pin "2") (pinfunction "PWR-GND_2") (pintype "bidirectional"))
    )
    (net (code "59") (name "REVERB_RETURN_B") (class "Default")
      (node (ref "IC102") (pin "3") (pinfunction "+IN_3") (pintype "input"))
      (node (ref "J2") (pin "4") (pinfunction "4_4") (pintype "passive"))
      (node (ref "JP102") (pin "2") (pinfunction "2_2") (pintype "passive"))
    )
    (net (code "60") (name "REVERB_RETURN_F") (class "Default")
      (node (ref "J1") (pin "4") (pinfunction "4_4") (pintype "passive"))
      (node (ref "X-FADE") (pin "P$2_SWITCH") (pinfunction "SWITCH_P$2_SWITCH") (pintype "passive"))
    )
    (net (code "61") (name "REVERB_SEND_B") (class "Default")
      (node (ref "C5") (pin "2") (pinfunction "2_2") (pintype "passive"))
      (node (ref "IC102") (pin "10") (pinfunction "+IN_10") (pintype "input"))
      (node (ref "R101") (pin "1") (pinfunction "1_1") (pintype "passive"))
      (node (ref "R18") (pin "2") (pinfunction "2_2") (pintype "passive"))
      (node (ref "R19") (pin "2") (pinfunction "2_2") (pintype "passive"))
      (node (ref "U7") (pin "1") (pinfunction "OUT_1") (pintype "output"))
    )
    (net (code "62") (name "TRIM_B") (class "Default")
      (node (ref "C101") (pin "2") (pinfunction "-_2") (pintype "passive"))
      (node (ref "JP104") (pin "3") (pinfunction "3_3") (pintype "passive"))
    )
    (net (code "63") (name "TRIM_F") (class "Default")
      (node (ref "JP2") (pin "3") (pinfunction "3_3") (pintype "passive"))
      (node (ref "VR1") (pin "1") (pinfunction "1_1") (pintype "passive"))
    )
    (net (code "64") (name "VAC_AN_B") (class "Default")
      (node (ref "JP104") (pin "1") (pinfunction "1_1") (pintype "passive"))
      (node (ref "V$101") (pin "LED+") (pinfunction "LED+_LED+") (pintype "passive"))
    )
    (net (code "65") (name "VAC_AN_F") (class "Default")
      (node (ref "JP2") (pin "1") (pinfunction "1_1") (pintype "passive"))
      (node (ref "LED1") (pin "K") (pinfunction "C_K") (pintype "passive"))
    )
    (net (code "66") (name "VAC_CA_B") (class "Default")
      (node (ref "JP104") (pin "2") (pinfunction "2_2") (pintype "passive"))
      (node (ref "V$101") (pin "LED-") (pinfunction "LED-_LED-") (pintype "passive"))
    )
    (net (code "67") (name "VAC_CA_F") (class "Default")
      (node (ref "JP2") (pin "2") (pinfunction "2_2") (pintype "passive"))
      (node (ref "R24") (pin "1") (pinfunction "1_1") (pintype "passive"))
      (node (ref "U2") (pin "2") (pinfunction "-IN_2") (pintype "input"))
    )
    (net (code "68") (name "WET_B") (class "Default")
      (node (ref "IC102") (pin "1") (pinfunction "OUT_1") (pintype "output"))
      (node (ref "IC102") (pin "2") (pinfunction "-IN_2") (pintype "input"))
      (node (ref "J2") (pin "2") (pinfunction "2_2") (pintype "passive"))
    )
    (net (code "69") (name "WET_F") (class "Default")
      (node (ref "IN_2") (pin "P$2_SWITCH") (pinfunction "SWITCH_P$2_SWITCH") (pintype "passive"))
      (node (ref "J1") (pin "2") (pinfunction "2_2") (pintype "passive"))
      (node (ref "WET_OUT") (pin "P$1_TIP") (pinfunction "TIP_P$1_TIP") (pintype "passive"))
    )
    (net (code "70") (name "XFADE_B") (class "Default")
      (node (ref "IC103") (pin "3") (pinfunction "+IN_3") (pintype "input"))
      (node (ref "J2") (pin "3") (pinfunction "3_3") (pintype "passive"))
    )
    (net (code "71") (name "XFADE_F") (class "Default")
      (node (ref "J1") (pin "3") (pinfunction "3_3") (pintype "passive"))
      (node (ref "X-FADE") (pin "P$1_TIP") (pinfunction "TIP_P$1_TIP") (pintype "passive"))
    )
    (net (code "72") (name "unconnected-(CV-SWITCH-PadP$2_SWITCH)") (class "Default")
      (node (ref "CV") (pin "P$2_SWITCH") (pinfunction "SWITCH_P$2_SWITCH") (pintype "passive"))
    )
    (net (code "73") (name "unconnected-(IN_1-SWITCH-PadP$2_SWITCH)") (class "Default")
      (node (ref "IN_1") (pin "P$2_SWITCH") (pinfunction "SWITCH_P$2_SWITCH") (pintype "passive"))
    )
    (net (code "74") (name "unconnected-(MIX_OUT-SWITCH-PadP$2_SWITCH)") (class "Default")
      (node (ref "MIX_OUT") (pin "P$2_SWITCH") (pinfunction "SWITCH_P$2_SWITCH") (pintype "passive"))
    )
    (net (code "75") (name "unconnected-(WET_OUT-SWITCH-PadP$2_SWITCH)") (class "Default")
      (node (ref "WET_OUT") (pin "P$2_SWITCH") (pinfunction "SWITCH_P$2_SWITCH") (pintype "passive"))
    )
    (net (code "76") (name "unconnected-(X101-2-PadS@1)") (class "Default")
      (node (ref "X101") (pin "S@1") (pinfunction "2_S@1") (pintype "passive"))
    )
    (net (code "77") (name "unconnected-(X101-2-PadS@2)") (class "Default")
      (node (ref "X101") (pin "S@2") (pinfunction "2_S@2") (pintype "passive"))
    )
    (net (code "78") (name "unconnected-(X101-2-PadS@3)") (class "Default")
      (node (ref "X101") (pin "S@3") (pinfunction "2_S@3") (pintype "passive"))
    )
    (net (code "79") (name "unconnected-(X102-2-PadS@1)") (class "Default")
      (node (ref "X102") (pin "S@1") (pinfunction "2_S@1") (pintype "passive"))
    )
    (net (code "80") (name "unconnected-(X102-2-PadS@2)") (class "Default")
      (node (ref "X102") (pin "S@2") (pinfunction "2_S@2") (pintype "passive"))
    )
    (net (code "81") (name "unconnected-(X102-2-PadS@3)") (class "Default")
      (node (ref "X102") (pin "S@3") (pinfunction "2_S@3") (pintype "passive"))
    )
  )
)
